# Microcontroller_Zero.net
KiCad netlist of a schematic drawn in Altium Designer
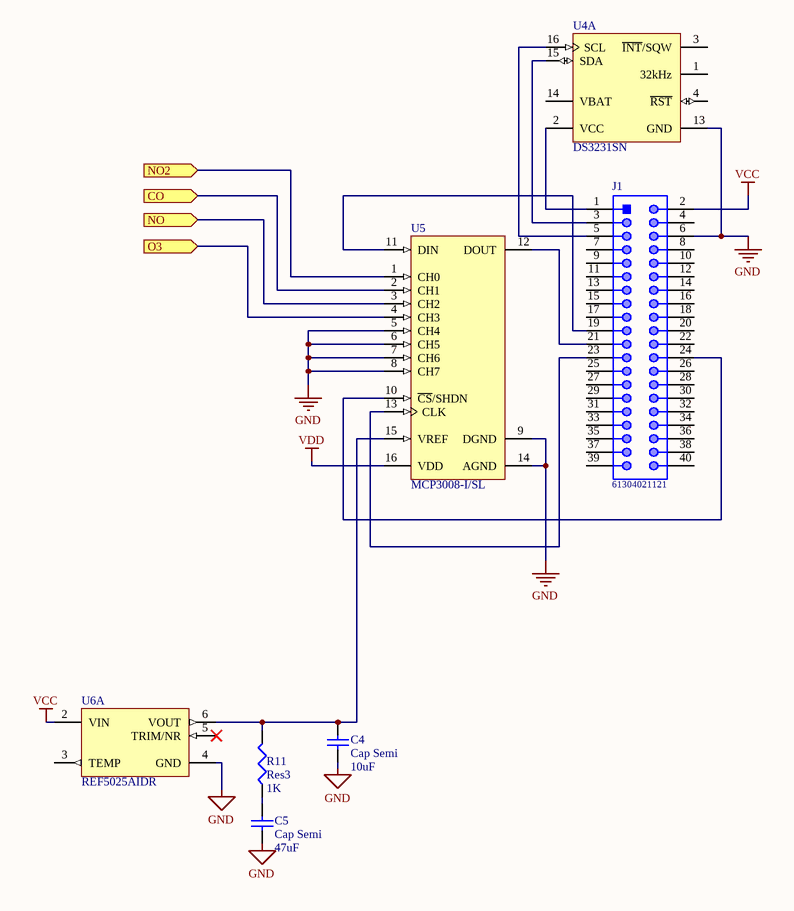
[diagram p0: Microcontroller+Zero.SchDoc]

(export (version "E")
  (design (tool "Eeschema 10.0.6"))
  (components
    (comp (ref "C4")
      (value "Cap Semi")
      (footprint "C1206")
      (description "Capacitor (Semiconductor SIM Model)")
      (fields (field (name "ALTIUM_VALUE") "10uF") (field (name "PUBLISHER") "Altium Limited"))
      (libsource (lib "Miscellaneous Devices") (part "Cap Semi"))
    )
    (comp (ref "C5")
      (value "Cap Semi")
      (footprint "C1206")
      (description "Capacitor (Semiconductor SIM Model)")
      (fields (field (name "ALTIUM_VALUE") "47uF") (field (name "PUBLISHER") "Altium Limited"))
      (libsource (lib "Miscellaneous Devices") (part "Cap Semi"))
    )
    (comp (ref "J1")
      (value "61304021121")
      (footprint "61304021121")
      (description "THT Vertical Pin Header WR-PHD, Pitch 2.54 mm, Dual Row, 40 pins")
      (fields (field (name "MANUFACTURER") "Wurth Elektronik") (field (name "PUBLISHER") "WurthElektronik"))
      (libsource (lib "Altium Content Vault") (part "WE-CN-2P-M-R40"))
    )
    (comp (ref "R11")
      (value "Res3")
      (footprint "J1-0603")
      (description "Resistor")
      (fields (field (name "ALTIUM_VALUE") "1K") (field (name "PUBLISHER") "Altium Limited"))
      (libsource (lib "Miscellaneous Devices") (part "Res3"))
    )
    (comp (ref "U4")
      (value "DS3231SN")
      (footprint "W16-H2_L")
      (description "Extremely Accurate I2C-Integrated Real-Time Clock/TCXO/Crystal, 16-Pin SO, -40 to 85 degC")
      (libsource (lib "Altium Content Vault") (part "MAX-RTC-16-DS3231S-W16#H2"))
    )
    (comp (ref "U5")
      (value "MCP3008-I/SL")
      (footprint "SOIC-SL16_L")
      (libsource (lib "Altium Content Vault") (part "CON-ADC-MCP3008-16"))
    )
    (comp (ref "U6")
      (value "REF5025AIDR")
      (footprint "D0008A_L")
      (fields (field (name "MANUFACTURER") "Texas Instruments"))
      (libsource (lib "Altium Content Vault") (part "TI-REF5025D8"))
    )
  )
  (nets
    (net (code "1") (name "/CO") (class "Default")
      (node (ref "U5") (pin "2") (pinfunction "CH1_2") (pintype "input"))
    )
    (net (code "2") (name "/NO") (class "Default")
      (node (ref "U5") (pin "3") (pinfunction "CH2_3") (pintype "input"))
    )
    (net (code "3") (name "/NO2") (class "Default")
      (node (ref "U5") (pin "1") (pinfunction "CH0_1") (pintype "input"))
    )
    (net (code "4") (name "/O3") (class "Default")
      (node (ref "U5") (pin "4") (pinfunction "CH3_4") (pintype "input"))
    )
    (net (code "5") (name "GND") (class "Default")
      (node (ref "C4") (pin "1") (pinfunction "1_1") (pintype "passive"))
      (node (ref "C5") (pin "1") (pinfunction "1_1") (pintype "passive"))
      (node (ref "J1") (pin "6") (pinfunction "6_6") (pintype "passive"))
      (node (ref "U4") (pin "13") (pinfunction "GND_13") (pintype "power_in"))
      (node (ref "U5") (pin "14") (pinfunction "AGND_14") (pintype "power_in"))
      (node (ref "U5") (pin "5") (pinfunction "CH4_5") (pintype "input"))
      (node (ref "U5") (pin "6") (pinfunction "CH5_6") (pintype "input"))
      (node (ref "U5") (pin "7") (pinfunction "CH6_7") (pintype "input"))
      (node (ref "U5") (pin "8") (pinfunction "CH7_8") (pintype "input"))
      (node (ref "U5") (pin "9") (pinfunction "DGND_9") (pintype "power_in"))
      (node (ref "U6") (pin "4") (pinfunction "GND_4") (pintype "power_in"))
    )
    (net (code "6") (name "Net-(C5-Pad2)") (class "Default")
      (node (ref "C5") (pin "2") (pinfunction "2_2") (pintype "passive"))
      (node (ref "R11") (pin "1") (pinfunction "1_1") (pintype "passive"))
    )
    (net (code "7") (name "Net-(U4A-SCL)") (class "Default")
      (node (ref "J1") (pin "5") (pinfunction "5_5") (pintype "passive"))
      (node (ref "U4") (pin "16") (pinfunction "SCL_16") (pintype "input"))
    )
    (net (code "8") (name "Net-(U4A-SDA)") (class "Default")
      (node (ref "J1") (pin "3") (pinfunction "3_3") (pintype "passive"))
      (node (ref "U4") (pin "15") (pinfunction "SDA_15") (pintype "bidirectional"))
    )
    (net (code "9") (name "Net-(U4A-VCC)") (class "Default")
      (node (ref "J1") (pin "1") (pinfunction "1_1") (pintype "passive"))
      (node (ref "U4") (pin "2") (pinfunction "VCC_2") (pintype "power_in"))
    )
    (net (code "10") (name "Net-(U5-CLK)") (class "Default")
      (node (ref "J1") (pin "23") (pinfunction "23_23") (pintype "passive"))
      (node (ref "U5") (pin "13") (pinfunction "CLK_13") (pintype "input"))
    )
    (net (code "11") (name "Net-(U5-DIN)") (class "Default")
      (node (ref "J1") (pin "19") (pinfunction "19_19") (pintype "passive"))
      (node (ref "U5") (pin "11") (pinfunction "DIN_11") (pintype "input"))
    )
    (net (code "12") (name "Net-(U5-DOUT)") (class "Default")
      (node (ref "J1") (pin "21") (pinfunction "21_21") (pintype "passive"))
      (node (ref "U5") (pin "12") (pinfunction "DOUT_12") (pintype "tri_state"))
    )
    (net (code "13") (name "Net-(U5-VREF)") (class "Default")
      (node (ref "C4") (pin "2") (pinfunction "2_2") (pintype "passive"))
      (node (ref "R11") (pin "2") (pinfunction "2_2") (pintype "passive"))
      (node (ref "U5") (pin "15") (pinfunction "VREF_15") (pintype "input"))
      (node (ref "U6") (pin "6") (pinfunction "VOUT_6") (pintype "output"))
    )
    (net (code "14") (name "Net-(U5-~{CS}{slash}SHDN)") (class "Default")
      (node (ref "J1") (pin "24") (pinfunction "24_24") (pintype "passive"))
      (node (ref "U5") (pin "10") (pinfunction "~{CS}/SHDN_10") (pintype "input"))
    )
    (net (code "15") (name "VCC") (class "Default")
      (node (ref "J1") (pin "2") (pinfunction "2_2") (pintype "passive"))
      (node (ref "U6") (pin "2") (pinfunction "VIN_2") (pintype "power_in"))
    )
    (net (code "16") (name "VDD") (class "Default")
      (node (ref "U5") (pin "16") (pinfunction "VDD_16") (pintype "power_in"))
    )
    (net (code "17") (name "unconnected-(J1-Pad4)") (class "Default")
      (node (ref "J1") (pin "4") (pinfunction "4_4") (pintype "passive"))
    )
    (net (code "18") (name "unconnected-(J1-Pad7)") (class "Default")
      (node (ref "J1") (pin "7") (pinfunction "7_7") (pintype "passive"))
    )
    (net (code "19") (name "unconnected-(J1-Pad8)") (class "Default")
      (node (ref "J1") (pin "8") (pinfunction "8_8") (pintype "passive"))
    )
    (net (code "20") (name "unconnected-(J1-Pad9)") (class "Default")
      (node (ref "J1") (pin "9") (pinfunction "9_9") (pintype "passive"))
    )
    (net (code "21") (name "unconnected-(J1-Pad10)") (class "Default")
      (node (ref "J1") (pin "10") (pinfunction "10_10") (pintype "passive"))
    )
    (net (code "22") (name "unconnected-(J1-Pad11)") (class "Default")
      (node (ref "J1") (pin "11") (pinfunction "11_11") (pintype "passive"))
    )
    (net (code "23") (name "unconnected-(J1-Pad12)") (class "Default")
      (node (ref "J1") (pin "12") (pinfunction "12_12") (pintype "passive"))
    )
    (net (code "24") (name "unconnected-(J1-Pad13)") (class "Default")
      (node (ref "J1") (pin "13") (pinfunction "13_13") (pintype "passive"))
    )
    (net (code "25") (name "unconnected-(J1-Pad14)") (class "Default")
      (node (ref "J1") (pin "14") (pinfunction "14_14") (pintype "passive"))
    )
    (net (code "26") (name "unconnected-(J1-Pad15)") (class "Default")
      (node (ref "J1") (pin "15") (pinfunction "15_15") (pintype "passive"))
    )
    (net (code "27") (name "unconnected-(J1-Pad16)") (class "Default")
      (node (ref "J1") (pin "16") (pinfunction "16_16") (pintype "passive"))
    )
    (net (code "28") (name "unconnected-(J1-Pad17)") (class "Default")
      (node (ref "J1") (pin "17") (pinfunction "17_17") (pintype "passive"))
    )
    (net (code "29") (name "unconnected-(J1-Pad18)") (class "Default")
      (node (ref "J1") (pin "18") (pinfunction "18_18") (pintype "passive"))
    )
    (net (code "30") (name "unconnected-(J1-Pad20)") (class "Default")
      (node (ref "J1") (pin "20") (pinfunction "20_20") (pintype "passive"))
    )
    (net (code "31") (name "unconnected-(J1-Pad22)") (class "Default")
      (node (ref "J1") (pin "22") (pinfunction "22_22") (pintype "passive"))
    )
    (net (code "32") (name "unconnected-(J1-Pad25)") (class "Default")
      (node (ref "J1") (pin "25") (pinfunction "25_25") (pintype "passive"))
    )
    (net (code "33") (name "unconnected-(J1-Pad26)") (class "Default")
      (node (ref "J1") (pin "26") (pinfunction "26_26") (pintype "passive"))
    )
    (net (code "34") (name "unconnected-(J1-Pad27)") (class "Default")
      (node (ref "J1") (pin "27") (pinfunction "27_27") (pintype "passive"))
    )
    (net (code "35") (name "unconnected-(J1-Pad28)") (class "Default")
      (node (ref "J1") (pin "28") (pinfunction "28_28") (pintype "passive"))
    )
    (net (code "36") (name "unconnected-(J1-Pad29)") (class "Default")
      (node (ref "J1") (pin "29") (pinfunction "29_29") (pintype "passive"))
    )
    (net (code "37") (name "unconnected-(J1-Pad30)") (class "Default")
      (node (ref "J1") (pin "30") (pinfunction "30_30") (pintype "passive"))
    )
    (net (code "38") (name "unconnected-(J1-Pad31)") (class "Default")
      (node (ref "J1") (pin "31") (pinfunction "31_31") (pintype "passive"))
    )
    (net (code "39") (name "unconnected-(J1-Pad32)") (class "Default")
      (node (ref "J1") (pin "32") (pinfunction "32_32") (pintype "passive"))
    )
    (net (code "40") (name "unconnected-(J1-Pad33)") (class "Default")
      (node (ref "J1") (pin "33") (pinfunction "33_33") (pintype "passive"))
    )
    (net (code "41") (name "unconnected-(J1-Pad34)") (class "Default")
      (node (ref "J1") (pin "34") (pinfunction "34_34") (pintype "passive"))
    )
    (net (code "42") (name "unconnected-(J1-Pad35)") (class "Default")
      (node (ref "J1") (pin "35") (pinfunction "35_35") (pintype "passive"))
    )
    (net (code "43") (name "unconnected-(J1-Pad36)") (class "Default")
      (node (ref "J1") (pin "36") (pinfunction "36_36") (pintype "passive"))
    )
    (net (code "44") (name "unconnected-(J1-Pad37)") (class "Default")
      (node (ref "J1") (pin "37") (pinfunction "37_37") (pintype "passive"))
    )
    (net (code "45") (name "unconnected-(J1-Pad38)") (class "Default")
      (node (ref "J1") (pin "38") (pinfunction "38_38") (pintype "passive"))
    )
    (net (code "46") (name "unconnected-(J1-Pad39)") (class "Default")
      (node (ref "J1") (pin "39") (pinfunction "39_39") (pintype "passive"))
    )
    (net (code "47") (name "unconnected-(J1-Pad40)") (class "Default")
      (node (ref "J1") (pin "40") (pinfunction "40_40") (pintype "passive"))
    )
    (net (code "48") (name "unconnected-(U4A-32kHz-Pad1)") (class "Default")
      (node (ref "U4") (pin "1") (pinfunction "32kHz_1") (pintype "open_collector"))
    )
    (net (code "49") (name "unconnected-(U4A-VBAT-Pad14)") (class "Default")
      (node (ref "U4") (pin "14") (pinfunction "VBAT_14") (pintype "power_in"))
    )
    (net (code "50") (name "unconnected-(U4A-~{INT}{slash}SQW-Pad3)") (class "Default")
      (node (ref "U4") (pin "3") (pinfunction "~{INT}/SQW_3") (pintype "open_collector"))
    )
    (net (code "51") (name "unconnected-(U4A-~{RST}-Pad4)") (class "Default")
      (node (ref "U4") (pin "4") (pinfunction "~{RST}_4") (pintype "bidirectional"))
    )
    (net (code "52") (name "unconnected-(U6A-TEMP-Pad3)") (class "Default")
      (node (ref "U6") (pin "3") (pinfunction "TEMP_3") (pintype "output"))
    )
    (net (code "53") (name "unconnected-(U6A-TRIM{slash}NR-Pad5)") (class "Default")
      (node (ref "U6") (pin "5") (pinfunction "TRIM/NR_5") (pintype "input+no_connect"))
    )
  )
)
